# MBusUART-DIN.net
KiCad netlist of a schematic drawn in EAGLE
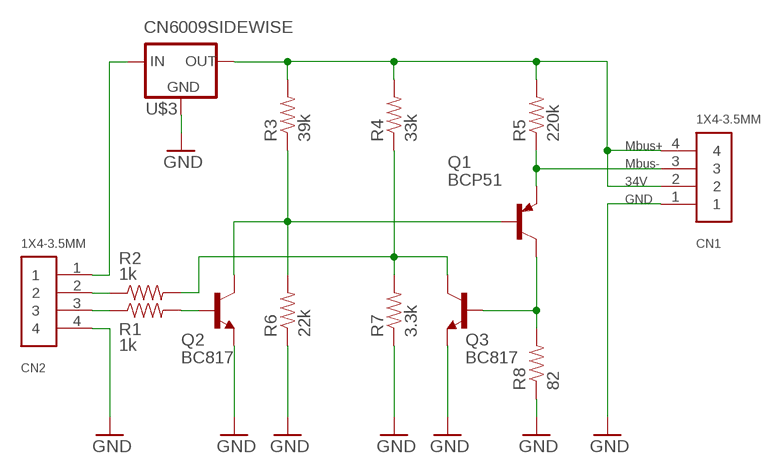
[diagram p0: schematic, sheet 1]

(export (version "E")
  (design (tool "Eeschema 10.0.6"))
  (components
    (comp (ref "CN1")
      (value "1X4-3.5MM")
      (footprint "eagle-import:1X04-3.5MM")
      (libsource (lib "eagle-import") (part "1X4-3.5MM"))
    )
    (comp (ref "CN2")
      (value "1X4-3.5MM")
      (footprint "eagle-import:1X04-3.5MM")
      (libsource (lib "eagle-import") (part "1X4-3.5MM"))
    )
    (comp (ref "Q1")
      (value "BCP51")
      (footprint "eagle-import:SOT223")
      (libsource (lib "eagle-import") (part "BCP51SOT223"))
    )
    (comp (ref "Q2")
      (value "BC817")
      (footprint "eagle-import:SOT23-BEC")
      (libsource (lib "eagle-import") (part "BC817SMD-16"))
    )
    (comp (ref "Q3")
      (value "BC817")
      (footprint "eagle-import:SOT23-BEC")
      (libsource (lib "eagle-import") (part "BC817SMD-16"))
    )
    (comp (ref "R1")
      (value "1k")
      (footprint "eagle-import:0805")
      (libsource (lib "eagle-import") (part "RESISTOR0805-RES"))
    )
    (comp (ref "R2")
      (value "1k")
      (footprint "eagle-import:0805")
      (libsource (lib "eagle-import") (part "RESISTOR0805-RES"))
    )
    (comp (ref "R3")
      (value "39k")
      (footprint "eagle-import:0805")
      (libsource (lib "eagle-import") (part "RESISTOR0805-RES"))
    )
    (comp (ref "R4")
      (value "33k")
      (footprint "eagle-import:0805")
      (libsource (lib "eagle-import") (part "RESISTOR0805-RES"))
    )
    (comp (ref "R5")
      (value "220k")
      (footprint "eagle-import:1206")
      (libsource (lib "eagle-import") (part "RESISTOR1206"))
    )
    (comp (ref "R6")
      (value "22k")
      (footprint "eagle-import:0805")
      (libsource (lib "eagle-import") (part "RESISTOR0805-RES"))
    )
    (comp (ref "R7")
      (value "3.3k")
      (footprint "eagle-import:0805")
      (libsource (lib "eagle-import") (part "RESISTOR0805-RES"))
    )
    (comp (ref "R8")
      (value "82")
      (footprint "eagle-import:1206")
      (libsource (lib "eagle-import") (part "RESISTOR1206"))
    )
    (comp (ref "U$3")
      (value "CN6009SIDEWISE")
      (footprint "eagle-import:CN6009-SIDEWISE")
      (libsource (lib "eagle-import") (part "CN6009SIDEWISE"))
    )
  )
  (nets
    (net (code "1") (name "/34V") (class "Default")
      (node (ref "CN1") (pin "2") (pinfunction "2_2") (pintype "bidirectional"))
      (node (ref "CN1") (pin "4") (pinfunction "4_4") (pintype "bidirectional"))
      (node (ref "R3") (pin "2") (pinfunction "2_2") (pintype "passive"))
      (node (ref "R4") (pin "2") (pinfunction "2_2") (pintype "passive"))
      (node (ref "R5") (pin "2") (pinfunction "2_2") (pintype "passive"))
      (node (ref "U$3") (pin "P$4") (pinfunction "OUT_P$4") (pintype "passive"))
      (node (ref "U$3") (pin "P$41") (pinfunction "OUT_P$41") (pintype "passive"))
    )
    (net (code "2") (name "GND") (class "Default")
      (node (ref "CN1") (pin "1") (pinfunction "1_1") (pintype "bidirectional"))
      (node (ref "CN2") (pin "4") (pinfunction "4_4") (pintype "bidirectional"))
      (node (ref "Q2") (pin "E") (pinfunction "E_E") (pintype "passive"))
      (node (ref "Q3") (pin "E") (pinfunction "E_E") (pintype "passive"))
      (node (ref "R6") (pin "1") (pinfunction "1_1") (pintype "passive"))
      (node (ref "R7") (pin "1") (pinfunction "1_1") (pintype "passive"))
      (node (ref "R8") (pin "1") (pinfunction "1_1") (pintype "passive"))
      (node (ref "U$3") (pin "P$1") (pinfunction "GND_P$1") (pintype "input"))
      (node (ref "U$3") (pin "P$11") (pinfunction "GND_P$11") (pintype "input"))
      (node (ref "U$3") (pin "P$2") (pinfunction "GND_P$2") (pintype "input"))
      (node (ref "U$3") (pin "P$21") (pinfunction "GND_P$21") (pintype "input"))
    )
    (net (code "3") (name "Net-(CN2-Pad1)") (class "Default")
      (node (ref "CN2") (pin "1") (pinfunction "1_1") (pintype "bidirectional"))
      (node (ref "U$3") (pin "P$3") (pinfunction "IN_P$3") (pintype "input"))
      (node (ref "U$3") (pin "P$31") (pinfunction "IN_P$31") (pintype "input"))
    )
    (net (code "4") (name "Net-(CN2-Pad2)") (class "Default")
      (node (ref "CN2") (pin "2") (pinfunction "2_2") (pintype "bidirectional"))
      (node (ref "R2") (pin "1") (pinfunction "1_1") (pintype "passive"))
    )
    (net (code "5") (name "Net-(CN2-Pad3)") (class "Default")
      (node (ref "CN2") (pin "3") (pinfunction "3_3") (pintype "bidirectional"))
      (node (ref "R1") (pin "1") (pinfunction "1_1") (pintype "passive"))
    )
    (net (code "6") (name "Net-(Q1-B)") (class "Default")
      (node (ref "Q1") (pin "1") (pinfunction "B_1") (pintype "passive"))
      (node (ref "Q2") (pin "C") (pinfunction "C_C") (pintype "passive"))
      (node (ref "R3") (pin "1") (pinfunction "1_1") (pintype "passive"))
      (node (ref "R6") (pin "2") (pinfunction "2_2") (pintype "passive"))
    )
    (net (code "7") (name "Net-(Q1-C-Pad2)") (class "Default")
      (node (ref "Q1") (pin "2") (pinfunction "C_2") (pintype "passive"))
      (node (ref "Q1") (pin "4") (pinfunction "C_4") (pintype "passive"))
      (node (ref "Q3") (pin "B") (pinfunction "B_B") (pintype "passive"))
      (node (ref "R8") (pin "2") (pinfunction "2_2") (pintype "passive"))
    )
    (net (code "8") (name "Net-(Q1-E)") (class "Default")
      (node (ref "CN1") (pin "3") (pinfunction "3_3") (pintype "bidirectional"))
      (node (ref "Q1") (pin "3") (pinfunction "E_3") (pintype "passive"))
      (node (ref "R5") (pin "1") (pinfunction "1_1") (pintype "passive"))
    )
    (net (code "9") (name "Net-(Q2-PadB)") (class "Default")
      (node (ref "Q2") (pin "B") (pinfunction "B_B") (pintype "passive"))
      (node (ref "R1") (pin "2") (pinfunction "2_2") (pintype "passive"))
    )
    (net (code "10") (name "Net-(Q3-PadC)") (class "Default")
      (node (ref "Q3") (pin "C") (pinfunction "C_C") (pintype "passive"))
      (node (ref "R2") (pin "2") (pinfunction "2_2") (pintype "passive"))
      (node (ref "R4") (pin "1") (pinfunction "1_1") (pintype "passive"))
      (node (ref "R7") (pin "2") (pinfunction "2_2") (pintype "passive"))
    )
  )
)
